# RFID2.net
KiCad netlist of a schematic drawn in Altium Designer
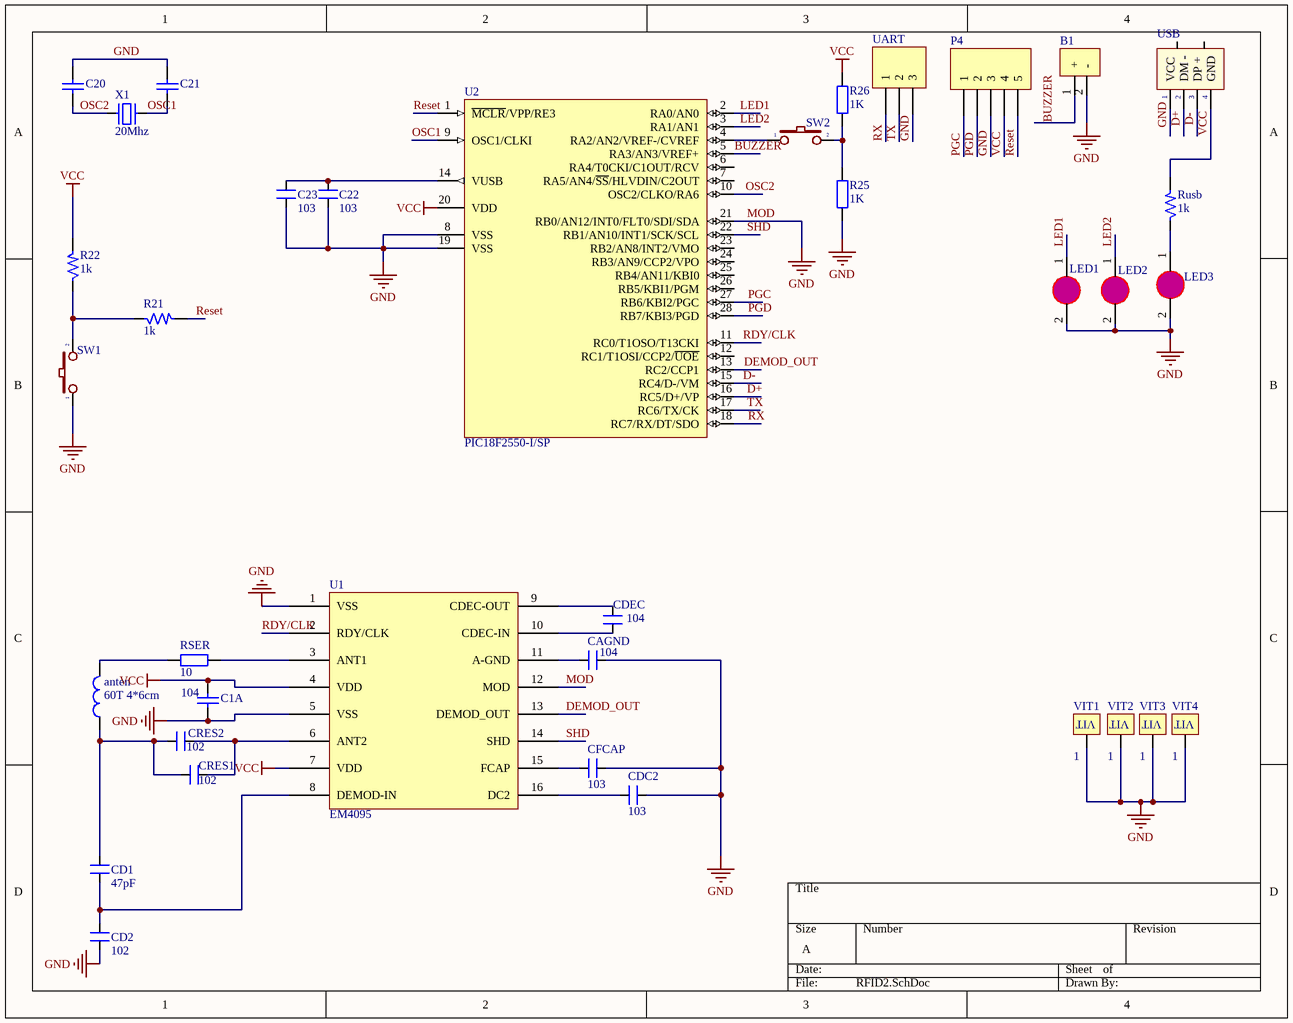
[diagram p0: RFID2.SchDoc]

(export (version "E")
  (design (tool "Eeschema 10.0.6"))
  (components
    (comp (ref "anten")
      (value "60T 4*6cm")
      (footprint "L/0.4")
      (description "Inductor")
      (libsource (lib "syhaunguyen") (part "L1"))
    )
    (comp (ref "B1")
      (value "Buzzer")
      (footprint "Buzzer_9x12mm")
      (libsource (lib "syhaunguyen") (part "Buzzer"))
    )
    (comp (ref "C1A")
      (value "104")
      (footprint "SM-0805")
      (description "Capacitor")
      (fields (field (name "PUBLISHER") "Altium Limited"))
      (libsource (lib "Schematic") (part "Cap"))
    )
    (comp (ref "C20")
      (value "27pf")
      (footprint "SM-0805")
      (description "Capacitor")
      (fields (field (name "PUBLISHER") "Altium Limited"))
      (libsource (lib "Schematic") (part "CapSMD"))
    )
    (comp (ref "C21")
      (value "27pf")
      (footprint "SM-0805")
      (description "Capacitor")
      (fields (field (name "PUBLISHER") "Altium Limited"))
      (libsource (lib "Schematic") (part "CapSMD"))
    )
    (comp (ref "C22")
      (value "103")
      (footprint "SM-0805")
      (description "Cap SMD")
      (libsource (lib "syhaunguyen") (part "CM"))
    )
    (comp (ref "C23")
      (value "103")
      (footprint "SM-0805")
      (description "Cap SMD")
      (libsource (lib "syhaunguyen") (part "CM"))
    )
    (comp (ref "CAGND")
      (value "104")
      (footprint "SM-0805")
      (description "Cap SMD")
      (libsource (lib "syhaunguyen") (part "CM"))
    )
    (comp (ref "CD1")
      (value "47pF")
      (footprint "SM-0805")
      (description "Cap SMD")
      (libsource (lib "syhaunguyen") (part "CM"))
    )
    (comp (ref "CD2")
      (value "102")
      (footprint "SM-0805")
      (description "Cap SMD")
      (libsource (lib "syhaunguyen") (part "CM"))
    )
    (comp (ref "CDC2")
      (value "103")
      (footprint "SM-0805")
      (description "Cap SMD")
      (libsource (lib "syhaunguyen") (part "CM"))
    )
    (comp (ref "CDEC")
      (value "104")
      (footprint "SM-0805")
      (description "Cap SMD")
      (libsource (lib "syhaunguyen") (part "CM"))
    )
    (comp (ref "CFCAP")
      (value "103")
      (footprint "SM-0805")
      (description "Cap SMD")
      (libsource (lib "syhaunguyen") (part "CM"))
    )
    (comp (ref "CRES1")
      (value "102")
      (footprint "SM-0805")
      (description "Cap SMD")
      (libsource (lib "syhaunguyen") (part "CM"))
    )
    (comp (ref "CRES2")
      (value "102")
      (footprint "SM-0805")
      (description "Cap SMD")
      (libsource (lib "syhaunguyen") (part "CM"))
    )
    (comp (ref "LED1")
      (value "LED3")
      (footprint "SM-0805")
      (description "LED 3mm")
      (libsource (lib "Schematic") (part "LEDSMD"))
    )
    (comp (ref "LED2")
      (value "~")
      (footprint "SM-0805")
      (description "LED 3mm")
      (libsource (lib "Schematic") (part "LEDSMD"))
    )
    (comp (ref "LED3")
      (value "~")
      (footprint "SM-0805")
      (description "LED 3mm")
      (libsource (lib "Schematic") (part "LEDSMD"))
    )
    (comp (ref "P4")
      (value "~")
      (footprint "CON5")
      (description "Header, 5-Pin")
      (fields (field (name "PUBLISHER") "Altium Limited"))
      (libsource (lib "Schematic") (part "Header 5"))
    )
    (comp (ref "R21")
      (value "1k")
      (footprint "SM-0805")
      (description "Resistor 1/4W")
      (libsource (lib "syhaunguyen") (part "R"))
    )
    (comp (ref "R22")
      (value "1k")
      (footprint "SM-0805")
      (description "Resistor 1/4W")
      (libsource (lib "syhaunguyen") (part "R"))
    )
    (comp (ref "R25")
      (value "1K")
      (footprint "SM-0805")
      (description "Resistor SMD")
      (libsource (lib "syhaunguyen") (part "RM"))
    )
    (comp (ref "R26")
      (value "1K")
      (footprint "SM-0805")
      (description "Resistor SMD")
      (libsource (lib "syhaunguyen") (part "RM"))
    )
    (comp (ref "RSER")
      (value "10")
      (footprint "SM-0805")
      (description "Resistor SMD")
      (libsource (lib "syhaunguyen") (part "RM"))
    )
    (comp (ref "Rusb")
      (value "1k")
      (footprint "SM-0805")
      (description "Resistor 1/4W")
      (libsource (lib "syhaunguyen") (part "R"))
    )
    (comp (ref "SW1")
      (value "SW")
      (footprint "SW2")
      (description "Switch button 2 pin")
      (libsource (lib "syhaunguyen") (part "SW2"))
    )
    (comp (ref "SW2")
      (value "SW")
      (footprint "SW2")
      (description "Switch button 2 pin")
      (libsource (lib "syhaunguyen") (part "SW2"))
    )
    (comp (ref "U1") (value "EM4095") (footprint "SO-16") (libsource (lib "binhbut") (part "EM4095")))
    (comp (ref "U2")
      (value "PIC18F2550-I/SP")
      (footprint "SPDIP300-SP28")
      (fields (field (name "PUBLISHER") "Altium Limited"))
      (libsource (lib "Microchip Microcontroller 8-Bit PIC18") (part "PIC18F2550-I/SP"))
    )
    (comp (ref "UART")
      (value "Header 3")
      (footprint "HDR1X3")
      (description "Header, 3-Pin")
      (fields (field (name "PUBLISHER") "Altium Limited"))
      (libsource (lib "Miscellaneous Connectors") (part "Header 3"))
    )
    (comp (ref "USB")
      (value "USB-S")
      (footprint "USB_B")
      (description "USB connector")
      (libsource (lib "syhaunguyen") (part "USB_S"))
    )
    (comp (ref "VIT1")
      (value "1")
      (footprint "VIT2")
      (description "Oc Vit")
      (libsource (lib "syhaunguyen") (part "VIT"))
    )
    (comp (ref "VIT2")
      (value "1")
      (footprint "VIT2")
      (description "Oc Vit")
      (libsource (lib "syhaunguyen") (part "VIT"))
    )
    (comp (ref "VIT3")
      (value "1")
      (footprint "VIT2")
      (description "Oc Vit")
      (libsource (lib "syhaunguyen") (part "VIT"))
    )
    (comp (ref "VIT4")
      (value "1")
      (footprint "VIT2")
      (description "Oc Vit")
      (libsource (lib "syhaunguyen") (part "VIT"))
    )
    (comp (ref "X1")
      (value "20Mhz")
      (footprint "XT2")
      (description "Crystal For all Crystal 2pin.")
      (libsource (lib "syhaunguyen") (part "XT2"))
    )
  )
  (nets
    (net (code "1") (name "/BUZZER") (class "Default")
      (node (ref "B1") (pin "1") (pinfunction "+_1") (pintype "passive"))
      (node (ref "U2") (pin "5") (pinfunction "RA3/AN3/VREF+_5") (pintype "bidirectional"))
    )
    (net (code "2") (name "/D+") (class "Default")
      (node (ref "U2") (pin "16") (pinfunction "RC5/D+/VP_16") (pintype "bidirectional"))
      (node (ref "USB") (pin "2") (pinfunction "DM_-_2") (pintype "passive"))
    )
    (net (code "3") (name "/D-") (class "Default")
      (node (ref "U2") (pin "15") (pinfunction "RC4/D-/VM_15") (pintype "bidirectional"))
      (node (ref "USB") (pin "3") (pinfunction "DP_+_3") (pintype "passive"))
    )
    (net (code "4") (name "/DEMOD_OUT") (class "Default")
      (node (ref "U1") (pin "13") (pinfunction "DEMOD_OUT_13") (pintype "passive"))
      (node (ref "U2") (pin "13") (pinfunction "RC2/CCP1_13") (pintype "bidirectional"))
    )
    (net (code "5") (name "/LED1") (class "Default")
      (node (ref "LED1") (pin "1") (pinfunction "A_1") (pintype "passive"))
      (node (ref "U2") (pin "2") (pinfunction "RA0/AN0_2") (pintype "bidirectional"))
    )
    (net (code "6") (name "/LED2") (class "Default")
      (node (ref "LED2") (pin "1") (pinfunction "A_1") (pintype "passive"))
      (node (ref "U2") (pin "3") (pinfunction "RA1/AN1_3") (pintype "bidirectional"))
    )
    (net (code "7") (name "/OSC1") (class "Default")
      (node (ref "C21") (pin "1") (pinfunction "1_1") (pintype "passive"))
      (node (ref "U2") (pin "9") (pinfunction "OSC1/CLKI_9") (pintype "input"))
      (node (ref "X1") (pin "2") (pinfunction "2_2") (pintype "passive"))
    )
    (net (code "8") (name "/OSC2") (class "Default")
      (node (ref "C20") (pin "1") (pinfunction "1_1") (pintype "passive"))
      (node (ref "U2") (pin "10") (pinfunction "OSC2/CLKO/RA6_10") (pintype "bidirectional"))
      (node (ref "X1") (pin "1") (pinfunction "1_1") (pintype "passive"))
    )
    (net (code "9") (name "/PGC") (class "Default")
      (node (ref "P4") (pin "1") (pinfunction "1_1") (pintype "passive"))
      (node (ref "U2") (pin "27") (pinfunction "RB6/KBI2/PGC_27") (pintype "bidirectional"))
    )
    (net (code "10") (name "/PGD") (class "Default")
      (node (ref "P4") (pin "2") (pinfunction "2_2") (pintype "passive"))
      (node (ref "U2") (pin "28") (pinfunction "RB7/KBI3/PGD_28") (pintype "bidirectional"))
    )
    (net (code "11") (name "/RDY{slash}CLK") (class "Default")
      (node (ref "U1") (pin "2") (pinfunction "RDY/CLK_2") (pintype "passive"))
      (node (ref "U2") (pin "11") (pinfunction "RC0/T1OSO/T13CKI_11") (pintype "bidirectional"))
    )
    (net (code "12") (name "/RX") (class "Default")
      (node (ref "U2") (pin "18") (pinfunction "RC7/RX/DT/SDO_18") (pintype "bidirectional"))
      (node (ref "UART") (pin "1") (pinfunction "1_1") (pintype "passive"))
    )
    (net (code "13") (name "/Reset") (class "Default")
      (node (ref "P4") (pin "5") (pinfunction "5_5") (pintype "passive"))
      (node (ref "R21") (pin "2") (pinfunction "2_2") (pintype "passive"))
      (node (ref "U2") (pin "1") (pinfunction "~{MCLR}/VPP/RE3_1") (pintype "input"))
    )
    (net (code "14") (name "/SHD") (class "Default")
      (node (ref "U1") (pin "14") (pinfunction "SHD_14") (pintype "passive"))
      (node (ref "U2") (pin "22") (pinfunction "RB1/AN10/INT1/SCK/SCL_22") (pintype "bidirectional"))
    )
    (net (code "15") (name "/TX") (class "Default")
      (node (ref "U2") (pin "17") (pinfunction "RC6/TX/CK_17") (pintype "bidirectional"))
      (node (ref "UART") (pin "2") (pinfunction "2_2") (pintype "passive"))
    )
    (net (code "16") (name "GND") (class "Default")
      (node (ref "B1") (pin "2") (pinfunction "-_2") (pintype "passive"))
      (node (ref "C1A") (pin "1") (pinfunction "1_1") (pintype "passive"))
      (node (ref "C20") (pin "2") (pinfunction "2_2") (pintype "passive"))
      (node (ref "C21") (pin "2") (pinfunction "2_2") (pintype "passive"))
      (node (ref "C22") (pin "1") (pinfunction "1_1") (pintype "passive"))
      (node (ref "C23") (pin "1") (pinfunction "1_1") (pintype "passive"))
      (node (ref "CAGND") (pin "2") (pinfunction "2_2") (pintype "passive"))
      (node (ref "CD2") (pin "1") (pinfunction "1_1") (pintype "passive"))
      (node (ref "CDC2") (pin "1") (pinfunction "1_1") (pintype "passive"))
      (node (ref "CFCAP") (pin "2") (pinfunction "2_2") (pintype "passive"))
      (node (ref "LED1") (pin "2") (pinfunction "K_2") (pintype "passive"))
      (node (ref "LED2") (pin "2") (pinfunction "K_2") (pintype "passive"))
      (node (ref "LED3") (pin "2") (pinfunction "K_2") (pintype "passive"))
      (node (ref "P4") (pin "3") (pinfunction "3_3") (pintype "passive"))
      (node (ref "R25") (pin "1") (pinfunction "1_1") (pintype "passive"))
      (node (ref "SW1") (pin "1") (pinfunction "1_1") (pintype "passive"))
      (node (ref "U1") (pin "1") (pinfunction "VSS_1") (pintype "power_in"))
      (node (ref "U1") (pin "12") (pinfunction "MOD_12") (pintype "passive"))
      (node (ref "U1") (pin "5") (pinfunction "VSS_5") (pintype "passive"))
      (node (ref "U2") (pin "19") (pinfunction "VSS_19") (pintype "power_in"))
      (node (ref "U2") (pin "21") (pinfunction "RB0/AN12/INT0/FLT0/SDI/SDA_21") (pintype "bidirectional"))
      (node (ref "U2") (pin "8") (pinfunction "VSS_8") (pintype "power_in"))
      (node (ref "UART") (pin "3") (pinfunction "3_3") (pintype "passive"))
      (node (ref "USB") (pin "1") (pinfunction "VCC_1") (pintype "passive"))
      (node (ref "VIT1") (pin "VIT1") (pinfunction "1_VIT1") (pintype "passive"))
      (node (ref "VIT2") (pin "VIT1") (pinfunction "1_VIT1") (pintype "passive"))
      (node (ref "VIT3") (pin "VIT1") (pinfunction "1_VIT1") (pintype "passive"))
      (node (ref "VIT4") (pin "VIT1") (pinfunction "1_VIT1") (pintype "passive"))
    )
    (net (code "17") (name "Net-(CD1-Pad2)") (class "Default")
      (node (ref "CD1") (pin "2") (pinfunction "2_2") (pintype "passive"))
      (node (ref "CRES1") (pin "1") (pinfunction "1_1") (pintype "passive"))
      (node (ref "CRES2") (pin "1") (pinfunction "1_1") (pintype "passive"))
      (node (ref "anten") (pin "1") (pinfunction "1_1") (pintype "passive"))
    )
    (net (code "18") (name "Net-(LED3-A)") (class "Default")
      (node (ref "LED3") (pin "1") (pinfunction "A_1") (pintype "passive"))
      (node (ref "Rusb") (pin "1") (pinfunction "1_1") (pintype "passive"))
    )
    (net (code "19") (name "Net-(R21-Pad1)") (class "Default")
      (node (ref "R21") (pin "1") (pinfunction "1_1") (pintype "passive"))
      (node (ref "R22") (pin "1") (pinfunction "1_1") (pintype "passive"))
      (node (ref "SW1") (pin "2") (pinfunction "2_2") (pintype "passive"))
    )
    (net (code "20") (name "Net-(R25-Pad2)") (class "Default")
      (node (ref "R25") (pin "2") (pinfunction "2_2") (pintype "passive"))
      (node (ref "R26") (pin "1") (pinfunction "1_1") (pintype "passive"))
      (node (ref "SW2") (pin "2") (pinfunction "2_2") (pintype "passive"))
    )
    (net (code "21") (name "Net-(RSER-Pad1)") (class "Default")
      (node (ref "RSER") (pin "1") (pinfunction "1_1") (pintype "passive"))
      (node (ref "anten") (pin "2") (pinfunction "2_2") (pintype "passive"))
    )
    (net (code "22") (name "Net-(U1-A-GND)") (class "Default")
      (node (ref "CAGND") (pin "1") (pinfunction "1_1") (pintype "passive"))
      (node (ref "U1") (pin "11") (pinfunction "A-GND_11") (pintype "passive"))
    )
    (net (code "23") (name "Net-(U1-ANT1)") (class "Default")
      (node (ref "RSER") (pin "2") (pinfunction "2_2") (pintype "passive"))
      (node (ref "U1") (pin "3") (pinfunction "ANT1_3") (pintype "passive"))
    )
    (net (code "24") (name "Net-(U1-ANT2)") (class "Default")
      (node (ref "CRES1") (pin "2") (pinfunction "2_2") (pintype "passive"))
      (node (ref "CRES2") (pin "2") (pinfunction "2_2") (pintype "passive"))
      (node (ref "U1") (pin "6") (pinfunction "ANT2_6") (pintype "passive"))
    )
    (net (code "25") (name "Net-(U1-CDEC-IN)") (class "Default")
      (node (ref "CDEC") (pin "1") (pinfunction "1_1") (pintype "passive"))
      (node (ref "U1") (pin "10") (pinfunction "CDEC-IN_10") (pintype "passive"))
    )
    (net (code "26") (name "Net-(U1-CDEC-OUT)") (class "Default")
      (node (ref "CDEC") (pin "2") (pinfunction "2_2") (pintype "passive"))
      (node (ref "U1") (pin "9") (pinfunction "CDEC-OUT_9") (pintype "passive"))
    )
    (net (code "27") (name "Net-(U1-DC2)") (class "Default")
      (node (ref "CDC2") (pin "2") (pinfunction "2_2") (pintype "passive"))
      (node (ref "U1") (pin "16") (pinfunction "DC2_16") (pintype "passive"))
    )
    (net (code "28") (name "Net-(U1-DEMOD-IN)") (class "Default")
      (node (ref "CD1") (pin "1") (pinfunction "1_1") (pintype "passive"))
      (node (ref "CD2") (pin "2") (pinfunction "2_2") (pintype "passive"))
      (node (ref "U1") (pin "8") (pinfunction "DEMOD-IN_8") (pintype "passive"))
    )
    (net (code "29") (name "Net-(U1-FCAP)") (class "Default")
      (node (ref "CFCAP") (pin "1") (pinfunction "1_1") (pintype "passive"))
      (node (ref "U1") (pin "15") (pinfunction "FCAP_15") (pintype "passive"))
    )
    (net (code "30") (name "Net-(U2-RA2{slash}AN2{slash}VREF-{slash}CVREF)") (class "Default")
      (node (ref "SW2") (pin "1") (pinfunction "1_1") (pintype "passive"))
      (node (ref "U2") (pin "4") (pinfunction "RA2/AN2/VREF-/CVREF_4") (pintype "bidirectional"))
    )
    (net (code "31") (name "Net-(U2-VUSB)") (class "Default")
      (node (ref "C22") (pin "2") (pinfunction "2_2") (pintype "passive"))
      (node (ref "C23") (pin "2") (pinfunction "2_2") (pintype "passive"))
      (node (ref "U2") (pin "14") (pinfunction "VUSB_14") (pintype "output"))
    )
    (net (code "32") (name "VCC") (class "Default")
      (node (ref "C1A") (pin "2") (pinfunction "2_2") (pintype "passive"))
      (node (ref "P4") (pin "4") (pinfunction "4_4") (pintype "passive"))
      (node (ref "R22") (pin "2") (pinfunction "2_2") (pintype "passive"))
      (node (ref "R26") (pin "2") (pinfunction "2_2") (pintype "passive"))
      (node (ref "Rusb") (pin "2") (pinfunction "2_2") (pintype "passive"))
      (node (ref "U1") (pin "4") (pinfunction "VDD_4") (pintype "passive"))
      (node (ref "U1") (pin "7") (pinfunction "VDD_7") (pintype "passive"))
      (node (ref "U2") (pin "20") (pinfunction "VDD_20") (pintype "power_in"))
      (node (ref "USB") (pin "4") (pinfunction "GND_4") (pintype "passive"))
    )
    (net (code "33") (name "unconnected-(U2-RA4{slash}T0CKI{slash}C1OUT{slash}RCV-Pad6)") (class "Default")
      (node (ref "U2") (pin "6") (pinfunction "RA4/T0CKI/C1OUT/RCV_6") (pintype "bidirectional"))
    )
    (net (code "34") (name "unconnected-(U2-RA5{slash}AN4{slash}~{SS}{slash}HLVDIN{slash}C2OUT-Pad7)") (class "Default")
      (node (ref "U2") (pin "7") (pinfunction "RA5/AN4/~{SS}/HLVDIN/C2OUT_7") (pintype "bidirectional"))
    )
    (net (code "35") (name "unconnected-(U2-RB2{slash}AN8{slash}INT2{slash}VMO-Pad23)") (class "Default")
      (node (ref "U2") (pin "23") (pinfunction "RB2/AN8/INT2/VMO_23") (pintype "bidirectional"))
    )
    (net (code "36") (name "unconnected-(U2-RB3{slash}AN9{slash}CCP2{slash}VPO-Pad24)") (class "Default")
      (node (ref "U2") (pin "24") (pinfunction "RB3/AN9/CCP2/VPO_24") (pintype "bidirectional"))
    )
    (net (code "37") (name "unconnected-(U2-RB4{slash}AN11{slash}KBI0-Pad25)") (class "Default")
      (node (ref "U2") (pin "25") (pinfunction "RB4/AN11/KBI0_25") (pintype "bidirectional"))
    )
    (net (code "38") (name "unconnected-(U2-RB5{slash}KBI1{slash}PGM-Pad26)") (class "Default")
      (node (ref "U2") (pin "26") (pinfunction "RB5/KBI1/PGM_26") (pintype "bidirectional"))
    )
    (net (code "39") (name "unconnected-(U2-RC1{slash}T1OSI{slash}CCP2{slash}~{UOE}-Pad12)") (class "Default")
      (node (ref "U2") (pin "12") (pinfunction "RC1/T1OSI/CCP2/~{UOE}_12") (pintype "bidirectional"))
    )
    (net (code "40") (name "unconnected-(USB-Pad5)") (class "Default")
      (node (ref "USB") (pin "5") (pinfunction "5_5") (pintype "passive"))
    )
    (net (code "41") (name "unconnected-(USB-Pad6)") (class "Default")
      (node (ref "USB") (pin "6") (pinfunction "6_6") (pintype "passive"))
    )
  )
)
